# USBC_charger.net
KiCad netlist of a schematic drawn in Altium Designer
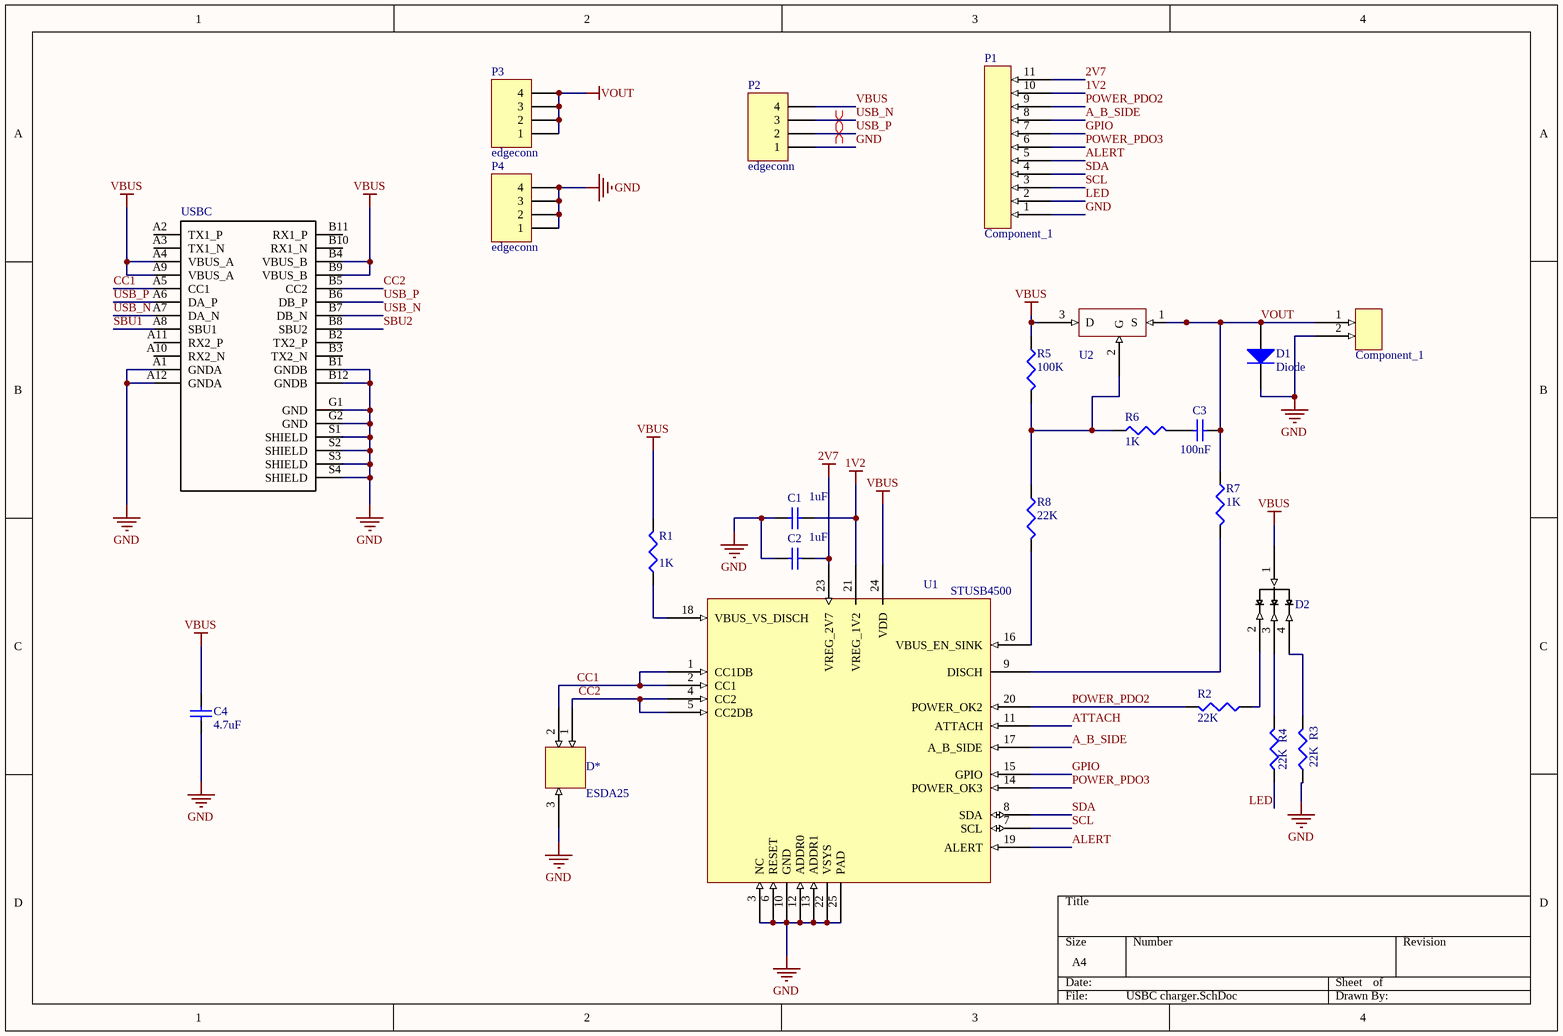
[diagram p0: USBC charger.SchDoc]

(export (version "E")
  (design (tool "Eeschema 10.0.6"))
  (components
    (comp (ref "*")
      (value "Component_1")
      (footprint "2pinSrewconnectyor")
      (libsource (lib "2pinconn") (part "Component_1"))
    )
    (comp (ref "C1")
      (value "1uF")
      (footprint "1608[0603]")
      (description "Capacitor (Semiconductor SIM Model)")
      (fields (field (name "Comment") "Cap Semi") (field (name "PUBLISHER") "Altium Limited"))
      (libsource (lib "Miscellaneous Devices") (part "Cap Semi"))
    )
    (comp (ref "C2")
      (value "1uF")
      (footprint "1608[0603]")
      (description "Capacitor (Semiconductor SIM Model)")
      (fields (field (name "Comment") "Cap Semi") (field (name "PUBLISHER") "Altium Limited"))
      (libsource (lib "Miscellaneous Devices") (part "Cap Semi"))
    )
    (comp (ref "C3")
      (value "100nF")
      (footprint "1608[0603]")
      (description "Capacitor (Semiconductor SIM Model)")
      (fields (field (name "Comment") "Cap Semi") (field (name "PUBLISHER") "Altium Limited"))
      (libsource (lib "Miscellaneous Devices") (part "Cap Semi"))
    )
    (comp (ref "C4")
      (value "4.7uF")
      (footprint "C2512")
      (description "Capacitor (Semiconductor SIM Model)")
      (fields (field (name "Comment") "Cap Semi") (field (name "PUBLISHER") "Altium Limited"))
      (libsource (lib "Miscellaneous Devices") (part "Cap Semi"))
    )
    (comp (ref "D*")
      (value "ESDA25")
      (footprint "SOT95P245X110-3N")
      (description "Generic Sot23 package")
      (libsource (lib "sot23") (part "Component_1"))
    )
    (comp (ref "D1")
      (value "Diode")
      (footprint "3.2X1.6X1.1")
      (description "Default Diode")
      (fields (field (name "PUBLISHER") "Altium Limited"))
      (libsource (lib "Miscellaneous Devices") (part "Diode"))
    )
    (comp (ref "D2")
      (value "SmollCree")
      (footprint "SmollLedCree")
      (libsource (lib "SmollCree") (part "SmollCree"))
    )
    (comp (ref "P1")
      (value "Component_1")
      (footprint "edgecon - large")
      (libsource (lib "11pinedgeconn") (part "Component_1"))
    )
    (comp (ref "P2")
      (value "edgeconn")
      (footprint "edgecon")
      (description "Header, 4-Pin")
      (fields (field (name "PUBLISHER") "Altium Limited"))
      (libsource (lib "edgeConn") (part "edgeconn"))
    )
    (comp (ref "P3")
      (value "edgeconn")
      (footprint "edgecon - power")
      (description "Header, 4-Pin")
      (fields (field (name "PUBLISHER") "Altium Limited"))
      (libsource (lib "edgeConn") (part "edgeconn"))
    )
    (comp (ref "P4")
      (value "edgeconn")
      (footprint "edgecon - power")
      (description "Header, 4-Pin")
      (fields (field (name "PUBLISHER") "Altium Limited"))
      (libsource (lib "edgeConn") (part "edgeconn"))
    )
    (comp (ref "R1")
      (value "1K")
      (footprint "J1-0603")
      (description "Resistor")
      (fields (field (name "Comment") "Res3") (field (name "PUBLISHER") "Altium Limited"))
      (libsource (lib "Miscellaneous Devices") (part "Res3"))
    )
    (comp (ref "R2")
      (value "22K")
      (footprint "J1-0603")
      (description "Resistor")
      (fields (field (name "Comment") "Res3") (field (name "PUBLISHER") "Altium Limited"))
      (libsource (lib "Miscellaneous Devices") (part "Res3"))
    )
    (comp (ref "R3")
      (value "22K")
      (footprint "J1-0603")
      (description "Resistor")
      (fields (field (name "Comment") "Res3") (field (name "PUBLISHER") "Altium Limited"))
      (libsource (lib "Miscellaneous Devices") (part "Res3"))
    )
    (comp (ref "R4")
      (value "22K")
      (footprint "J1-0603")
      (description "Resistor")
      (fields (field (name "Comment") "Res3") (field (name "PUBLISHER") "Altium Limited"))
      (libsource (lib "Miscellaneous Devices") (part "Res3"))
    )
    (comp (ref "R5")
      (value "100K")
      (footprint "J1-0603")
      (description "Resistor")
      (fields (field (name "Comment") "Res3") (field (name "PUBLISHER") "Altium Limited"))
      (libsource (lib "Miscellaneous Devices") (part "Res3"))
    )
    (comp (ref "R6")
      (value "1K")
      (footprint "J1-0603")
      (description "Resistor")
      (fields (field (name "Comment") "Res3") (field (name "PUBLISHER") "Altium Limited"))
      (libsource (lib "Miscellaneous Devices") (part "Res3"))
    )
    (comp (ref "R7")
      (value "1K")
      (footprint "J1-0603")
      (description "Resistor")
      (fields (field (name "Comment") "Res3") (field (name "PUBLISHER") "Altium Limited"))
      (libsource (lib "Miscellaneous Devices") (part "Res3"))
    )
    (comp (ref "R8")
      (value "22K")
      (footprint "J1-0603")
      (description "Resistor")
      (fields (field (name "Comment") "Res3") (field (name "PUBLISHER") "Altium Limited"))
      (libsource (lib "Miscellaneous Devices") (part "Res3"))
    )
    (comp (ref "U1")
      (value "STUSB4500")
      (footprint "QFN50P400X400X80_HS-25N")
      (description "stusb4500 PD ic")
      (libsource (lib "STUSB4500") (part "STUSB4500"))
    )
    (comp (ref "U2")
      (value "STL6P3LLH6")
      (footprint "powerflat")
      (libsource (lib "STL6P3LLH6") (part "STL6P3LLH6"))
    )
    (comp (ref "USBC")
      (value "2305018-2")
      (footprint "*TE_2305018-2_2305018-2(Primary)")
      (description "TYPE C Right Angle Sealable SMT IPX8 3.1 GEN 2 Wire to Board USB")
      (fields (field (name "MF") "TE Connectivity"))
      (libsource (lib "2305018-2") (part "2305018-2"))
    )
  )
  (nets
    (net (code "1") (name "/ALERT") (class "Default")
      (node (ref "P1") (pin "5") (pintype "input"))
      (node (ref "U1") (pin "19") (pinfunction "ALERT_19") (pintype "input"))
    )
    (net (code "2") (name "/ATTACH") (class "Default")
      (node (ref "U1") (pin "11") (pinfunction "ATTACH_11") (pintype "input"))
    )
    (net (code "3") (name "/A_B_SIDE") (class "Default")
      (node (ref "P1") (pin "8") (pintype "input"))
      (node (ref "U1") (pin "17") (pinfunction "A_B_SIDE_17") (pintype "input"))
    )
    (net (code "4") (name "/CC1") (class "Default")
      (node (ref "D*") (pin "2") (pintype "input"))
      (node (ref "U1") (pin "1") (pinfunction "CC1DB_1") (pintype "input"))
      (node (ref "U1") (pin "2") (pinfunction "CC1_2") (pintype "input"))
      (node (ref "USBC") (pin "A5") (pinfunction "CC1_A5") (pintype "passive"))
    )
    (net (code "5") (name "/CC2") (class "Default")
      (node (ref "D*") (pin "1") (pintype "input"))
      (node (ref "U1") (pin "4") (pinfunction "CC2_4") (pintype "input"))
      (node (ref "U1") (pin "5") (pinfunction "CC2DB_5") (pintype "input"))
      (node (ref "USBC") (pin "B5") (pinfunction "CC2_B5") (pintype "passive"))
    )
    (net (code "6") (name "/GPIO") (class "Default")
      (node (ref "P1") (pin "7") (pintype "input"))
      (node (ref "U1") (pin "15") (pinfunction "GPIO_15") (pintype "input"))
    )
    (net (code "7") (name "/LED") (class "Default")
      (node (ref "P1") (pin "2") (pintype "input"))
      (node (ref "R4") (pin "1") (pinfunction "1_1") (pintype "passive"))
    )
    (net (code "8") (name "/POWER_PDO2") (class "Default")
      (node (ref "P1") (pin "9") (pintype "input"))
      (node (ref "R2") (pin "2") (pinfunction "2_2") (pintype "passive"))
      (node (ref "U1") (pin "20") (pinfunction "POWER_OK2_20") (pintype "input"))
    )
    (net (code "9") (name "/POWER_PDO3") (class "Default")
      (node (ref "P1") (pin "6") (pintype "input"))
      (node (ref "U1") (pin "14") (pinfunction "POWER_OK3_14") (pintype "input"))
    )
    (net (code "10") (name "/SBU1") (class "Default")
      (node (ref "USBC") (pin "A8") (pinfunction "SBU1_A8") (pintype "passive"))
    )
    (net (code "11") (name "/SBU2") (class "Default")
      (node (ref "USBC") (pin "B8") (pinfunction "SBU2_B8") (pintype "passive"))
    )
    (net (code "12") (name "/SCL") (class "Default")
      (node (ref "P1") (pin "3") (pintype "input"))
      (node (ref "U1") (pin "7") (pinfunction "SCL_7") (pintype "bidirectional"))
    )
    (net (code "13") (name "/SDA") (class "Default")
      (node (ref "P1") (pin "4") (pintype "input"))
      (node (ref "U1") (pin "8") (pinfunction "SDA_8") (pintype "bidirectional"))
    )
    (net (code "14") (name "/USB_N") (class "Default")
      (node (ref "P2") (pin "3") (pinfunction "3_3") (pintype "passive"))
      (node (ref "USBC") (pin "A7") (pinfunction "DA_N_A7") (pintype "passive"))
      (node (ref "USBC") (pin "B7") (pinfunction "DB_N_B7") (pintype "passive"))
    )
    (net (code "15") (name "/USB_P") (class "Default")
      (node (ref "P2") (pin "2") (pinfunction "2_2") (pintype "passive"))
      (node (ref "USBC") (pin "A6") (pinfunction "DA_P_A6") (pintype "passive"))
      (node (ref "USBC") (pin "B6") (pinfunction "DB_P_B6") (pintype "passive"))
    )
    (net (code "16") (name "1V2") (class "Default")
      (node (ref "C1") (pin "2") (pinfunction "2_2") (pintype "passive"))
      (node (ref "P1") (pin "10") (pintype "input"))
      (node (ref "U1") (pin "21") (pinfunction "VREG_1V2_21") (pintype "power_in"))
    )
    (net (code "17") (name "2V7") (class "Default")
      (node (ref "C2") (pin "2") (pinfunction "2_2") (pintype "passive"))
      (node (ref "P1") (pin "11") (pintype "input"))
      (node (ref "U1") (pin "23") (pinfunction "VREG_2V7_23") (pintype "input"))
    )
    (net (code "18") (name "GND") (class "Default")
      (node (ref "*") (pin "2") (pintype "input"))
      (node (ref "C1") (pin "1") (pinfunction "1_1") (pintype "passive"))
      (node (ref "C2") (pin "1") (pinfunction "1_1") (pintype "passive"))
      (node (ref "C4") (pin "1") (pinfunction "1_1") (pintype "passive"))
      (node (ref "D*") (pin "3") (pintype "input"))
      (node (ref "D1") (pin "2") (pinfunction "K_2") (pintype "passive"))
      (node (ref "P1") (pin "1") (pintype "input"))
      (node (ref "P2") (pin "1") (pinfunction "1_1") (pintype "passive"))
      (node (ref "P4") (pin "1") (pinfunction "1_1") (pintype "passive"))
      (node (ref "P4") (pin "2") (pinfunction "2_2") (pintype "passive"))
      (node (ref "P4") (pin "3") (pinfunction "3_3") (pintype "passive"))
      (node (ref "P4") (pin "4") (pinfunction "4_4") (pintype "passive"))
      (node (ref "R3") (pin "1") (pinfunction "1_1") (pintype "passive"))
      (node (ref "U1") (pin "10") (pinfunction "GND_10") (pintype "power_in"))
      (node (ref "U1") (pin "12") (pinfunction "ADDR0_12") (pintype "input"))
      (node (ref "U1") (pin "13") (pinfunction "ADDR1_13") (pintype "input"))
      (node (ref "U1") (pin "22") (pinfunction "VSYS_22") (pintype "power_in"))
      (node (ref "U1") (pin "25") (pinfunction "PAD_25") (pintype "power_in"))
      (node (ref "U1") (pin "3") (pinfunction "NC_3") (pintype "input"))
      (node (ref "U1") (pin "6") (pinfunction "RESET_6") (pintype "input"))
      (node (ref "USBC") (pin "A1") (pinfunction "GNDA_A1") (pintype "passive"))
      (node (ref "USBC") (pin "A12") (pinfunction "GNDA_A12") (pintype "passive"))
      (node (ref "USBC") (pin "B1") (pinfunction "GNDB_B1") (pintype "passive"))
      (node (ref "USBC") (pin "B12") (pinfunction "GNDB_B12") (pintype "passive"))
      (node (ref "USBC") (pin "G1") (pinfunction "GND_G1") (pintype "power_in"))
      (node (ref "USBC") (pin "G2") (pinfunction "GND_G2") (pintype "power_in"))
      (node (ref "USBC") (pin "S1") (pinfunction "SHIELD_S1") (pintype "power_in"))
      (node (ref "USBC") (pin "S2") (pinfunction "SHIELD_S2") (pintype "power_in"))
      (node (ref "USBC") (pin "S3") (pinfunction "SHIELD_S3") (pintype "power_in"))
      (node (ref "USBC") (pin "S4") (pinfunction "SHIELD_S4") (pintype "power_in"))
    )
    (net (code "19") (name "Net-(C3-Pad1)") (class "Default")
      (node (ref "C3") (pin "1") (pinfunction "1_1") (pintype "passive"))
      (node (ref "R6") (pin "2") (pinfunction "2_2") (pintype "passive"))
    )
    (net (code "20") (name "Net-(D2-Blue)") (class "Default")
      (node (ref "D2") (pin "2") (pinfunction "Blue_2") (pintype "input"))
      (node (ref "R2") (pin "1") (pinfunction "1_1") (pintype "passive"))
    )
    (net (code "21") (name "Net-(D2-Pad3)") (class "Default")
      (node (ref "D2") (pin "3") (pintype "input"))
      (node (ref "R4") (pin "2") (pinfunction "2_2") (pintype "passive"))
    )
    (net (code "22") (name "Net-(D2-Pad4)") (class "Default")
      (node (ref "D2") (pin "4") (pintype "input"))
      (node (ref "R3") (pin "2") (pinfunction "2_2") (pintype "passive"))
    )
    (net (code "23") (name "Net-(U1-DISCH)") (class "Default")
      (node (ref "R7") (pin "2") (pinfunction "2_2") (pintype "passive"))
      (node (ref "U1") (pin "9") (pinfunction "DISCH_9") (pintype "power_in"))
    )
    (net (code "24") (name "Net-(U1-VBUS_EN_SINK)") (class "Default")
      (node (ref "R8") (pin "2") (pinfunction "2_2") (pintype "passive"))
      (node (ref "U1") (pin "16") (pinfunction "VBUS_EN_SINK_16") (pintype "input"))
    )
    (net (code "25") (name "Net-(U1-VBUS_VS_DISCH)") (class "Default")
      (node (ref "R1") (pin "1") (pinfunction "1_1") (pintype "passive"))
      (node (ref "U1") (pin "18") (pinfunction "VBUS_VS_DISCH_18") (pintype "input"))
    )
    (net (code "26") (name "Net-(U2-G)") (class "Default")
      (node (ref "R5") (pin "2") (pinfunction "2_2") (pintype "passive"))
      (node (ref "R6") (pin "1") (pinfunction "1_1") (pintype "passive"))
      (node (ref "R8") (pin "1") (pinfunction "1_1") (pintype "passive"))
      (node (ref "U2") (pin "2") (pinfunction "G_2") (pintype "input"))
    )
    (net (code "27") (name "VBUS") (class "Default")
      (node (ref "C4") (pin "2") (pinfunction "2_2") (pintype "passive"))
      (node (ref "D2") (pin "1") (pintype "input"))
      (node (ref "P2") (pin "4") (pinfunction "4_4") (pintype "passive"))
      (node (ref "R1") (pin "2") (pinfunction "2_2") (pintype "passive"))
      (node (ref "R5") (pin "1") (pinfunction "1_1") (pintype "passive"))
      (node (ref "U1") (pin "24") (pinfunction "VDD_24") (pintype "power_in"))
      (node (ref "U2") (pin "3") (pinfunction "D_3") (pintype "input"))
      (node (ref "USBC") (pin "A4") (pinfunction "VBUS_A_A4") (pintype "passive"))
      (node (ref "USBC") (pin "A9") (pinfunction "VBUS_A_A9") (pintype "passive"))
      (node (ref "USBC") (pin "B4") (pinfunction "VBUS_B_B4") (pintype "passive"))
      (node (ref "USBC") (pin "B9") (pinfunction "VBUS_B_B9") (pintype "passive"))
    )
    (net (code "28") (name "VOUT") (class "Default")
      (node (ref "*") (pin "1") (pintype "input"))
      (node (ref "C3") (pin "2") (pinfunction "2_2") (pintype "passive"))
      (node (ref "D1") (pin "1") (pinfunction "A_1") (pintype "passive"))
      (node (ref "P3") (pin "1") (pinfunction "1_1") (pintype "passive"))
      (node (ref "P3") (pin "2") (pinfunction "2_2") (pintype "passive"))
      (node (ref "P3") (pin "3") (pinfunction "3_3") (pintype "passive"))
      (node (ref "P3") (pin "4") (pinfunction "4_4") (pintype "passive"))
      (node (ref "R7") (pin "1") (pinfunction "1_1") (pintype "passive"))
      (node (ref "U2") (pin "1") (pinfunction "S_1") (pintype "input"))
    )
    (net (code "29") (name "unconnected-(USBC-RX1_N-PadB10)") (class "Default")
      (node (ref "USBC") (pin "B10") (pinfunction "RX1_N_B10") (pintype "passive"))
    )
    (net (code "30") (name "unconnected-(USBC-RX1_P-PadB11)") (class "Default")
      (node (ref "USBC") (pin "B11") (pinfunction "RX1_P_B11") (pintype "passive"))
    )
    (net (code "31") (name "unconnected-(USBC-RX2_N-PadA10)") (class "Default")
      (node (ref "USBC") (pin "A10") (pinfunction "RX2_N_A10") (pintype "passive"))
    )
    (net (code "32") (name "unconnected-(USBC-RX2_P-PadA11)") (class "Default")
      (node (ref "USBC") (pin "A11") (pinfunction "RX2_P_A11") (pintype "passive"))
    )
    (net (code "33") (name "unconnected-(USBC-TX1_N-PadA3)") (class "Default")
      (node (ref "USBC") (pin "A3") (pinfunction "TX1_N_A3") (pintype "passive"))
    )
    (net (code "34") (name "unconnected-(USBC-TX1_P-PadA2)") (class "Default")
      (node (ref "USBC") (pin "A2") (pinfunction "TX1_P_A2") (pintype "passive"))
    )
    (net (code "35") (name "unconnected-(USBC-TX2_N-PadB3)") (class "Default")
      (node (ref "USBC") (pin "B3") (pinfunction "TX2_N_B3") (pintype "passive"))
    )
    (net (code "36") (name "unconnected-(USBC-TX2_P-PadB2)") (class "Default")
      (node (ref "USBC") (pin "B2") (pinfunction "TX2_P_B2") (pintype "passive"))
    )
  )
)
